# Power_Sheet.net
KiCad netlist of a schematic drawn in Altium Designer
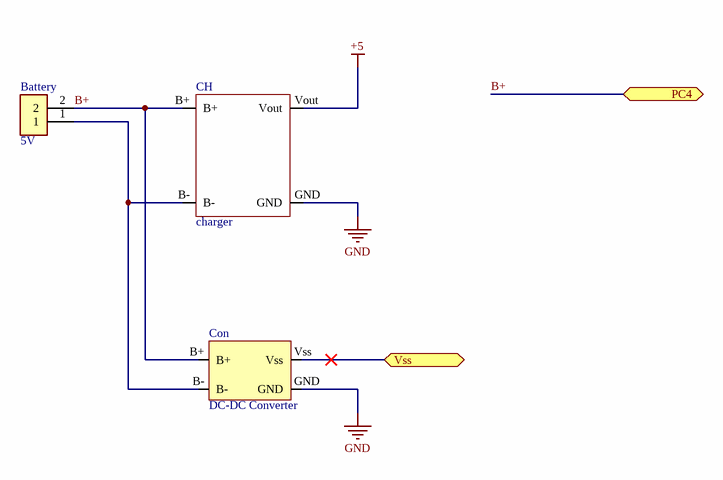
[diagram p0: Power_Sheet.SchDoc]

(export (version "E")
  (design (tool "Eeschema 10.0.6"))
  (components
    (comp (ref "Battery")
      (value "5V")
      (footprint "JST_B2B-PH-K-S(LF)(SN)")
      (description "Connector Header Through Hole 2 position 0.079 _2.00mm_")
      (fields (field (name "MF") "JST Sales") (field (name "MP") "B2B-PH-K-S_LF__SN_"))
      (libsource (lib "B2B-PH-K-S_LF__SN_") (part "B2B-PH-K-S(LF)(SN)"))
    )
    (comp (ref "CH")
      (value "charger")
      (footprint "1S_Charger")
      (libsource (lib "1S_Charger") (part "charger"))
    )
    (comp (ref "Con")
      (value "DC-DC Converter")
      (footprint "DC-DC Conv")
      (libsource (lib "DC_DC_Converter") (part "DC-DC Converter"))
    )
  )
  (nets
    (net (code "1") (name "+5") (class "Default")
      (node (ref "CH") (pin "Vout") (pinfunction "Vout_Vout") (pintype "passive"))
    )
    (net (code "2") (name "/B+") (class "Default")
      (node (ref "Battery") (pin "2") (pinfunction "2_2") (pintype "passive"))
      (node (ref "CH") (pin "B+") (pinfunction "B+_B+") (pintype "passive"))
      (node (ref "Con") (pin "B+") (pinfunction "B+_B+") (pintype "passive"))
    )
    (net (code "3") (name "/Vss") (class "Default")
      (node (ref "Con") (pin "Vss") (pinfunction "Vss_Vss") (pintype "passive"))
    )
    (net (code "4") (name "GND") (class "Default")
      (node (ref "CH") (pin "GND") (pinfunction "GND_GND") (pintype "passive"))
      (node (ref "Con") (pin "GND") (pinfunction "GND_GND") (pintype "passive"))
    )
    (net (code "5") (name "Net-(Battery-Pad1)") (class "Default")
      (node (ref "Battery") (pin "1") (pinfunction "1_1") (pintype "passive"))
      (node (ref "CH") (pin "B-") (pinfunction "B-_B-") (pintype "passive"))
      (node (ref "Con") (pin "B-") (pinfunction "B-_B-") (pintype "passive"))
    )
  )
)
